# Display_Control_UV.net
KiCad netlist of a schematic drawn in Altium Designer
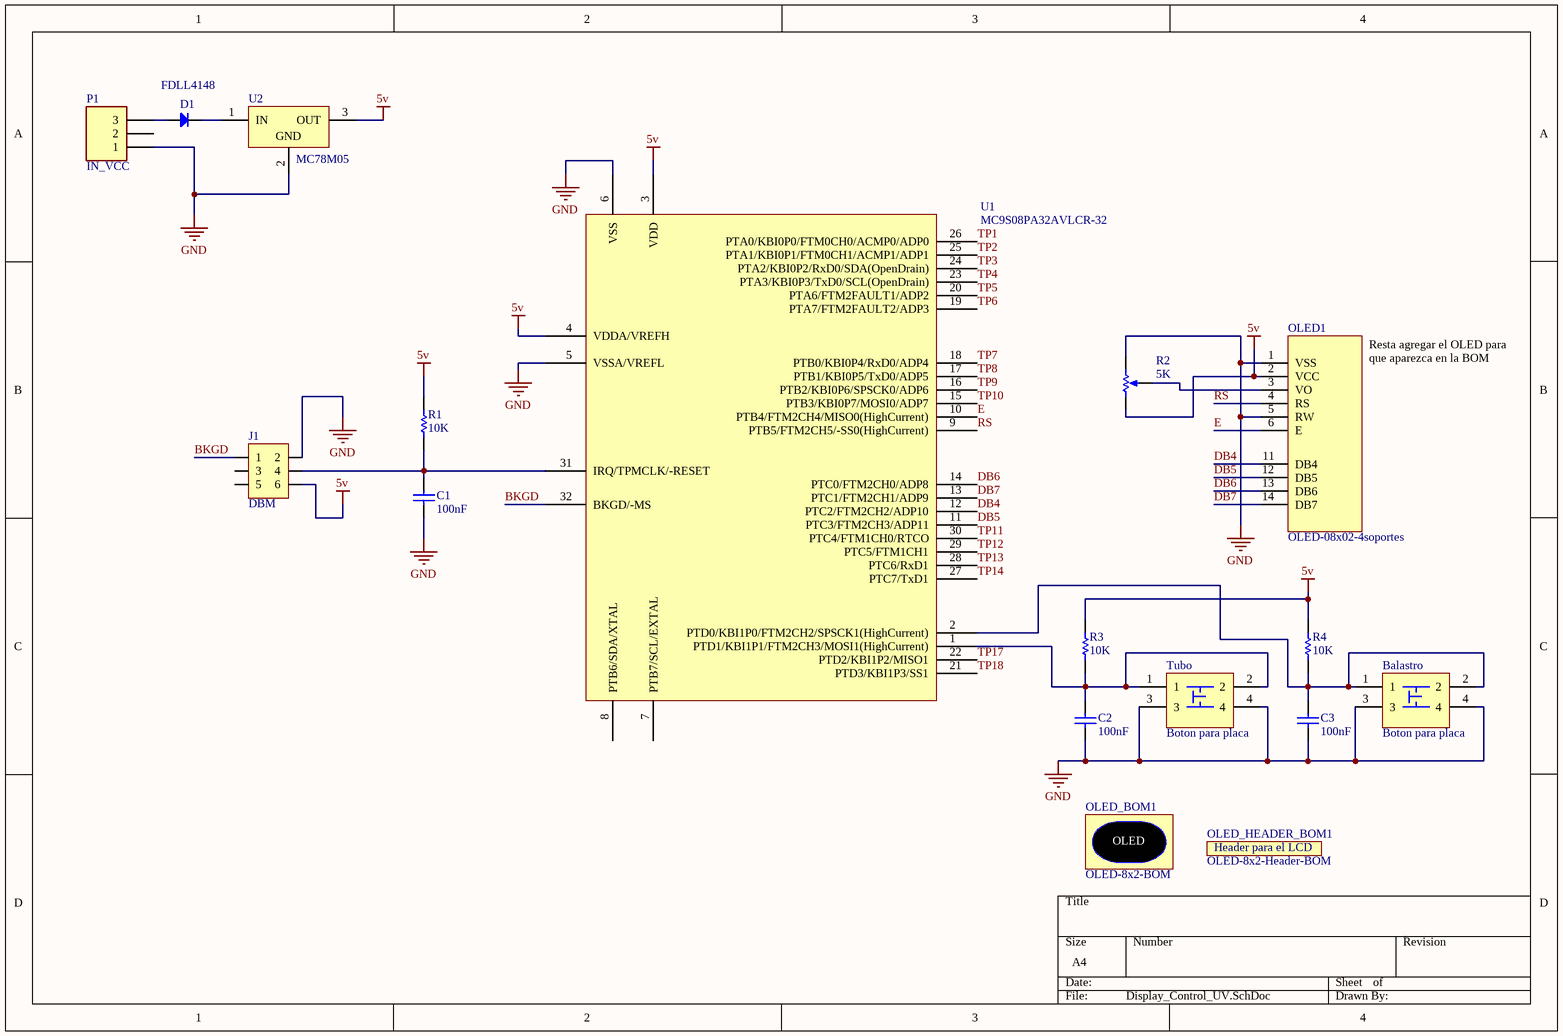
[diagram p0: Display_Control_UV.SchDoc]

(export (version "E")
  (design (tool "Eeschema 10.0.6"))
  (components
    (comp (ref "Balastro")
      (value "Boton para placa")
      (footprint "TactButton")
      (description "Ejemplo")
      (fields (field (name "PUBLISHER") "Altium Limited"))
      (libsource (lib "Nahuel_TH_BODY") (part "TactButton"))
    )
    (comp (ref "C1")
      (value "100nF")
      (footprint "Nahuel_SMD_Body:C_0603")
      (description "CAP CER 0.1UF 50V X7R 0603")
      (fields (field (name "PUBLISHER") "Altium Limited"))
      (libsource (lib "Nahuel_SMD_Body") (part "C_100nF_0603"))
    )
    (comp (ref "C2")
      (value "100nF")
      (footprint "Nahuel_SMD_Body:C_0603")
      (description "CAP CER 0.1UF 50V X7R 0603")
      (fields (field (name "PUBLISHER") "Altium Limited"))
      (libsource (lib "Nahuel_SMD_Body") (part "C_100nF_0603"))
    )
    (comp (ref "C3")
      (value "100nF")
      (footprint "Nahuel_SMD_Body:C_0603")
      (description "CAP CER 0.1UF 50V X7R 0603")
      (fields (field (name "PUBLISHER") "Altium Limited"))
      (libsource (lib "Nahuel_SMD_Body") (part "C_100nF_0603"))
    )
    (comp (ref "D1")
      (value "FDLL4148")
      (footprint "Nahuel_SMD_Body:SOD-80/MLL34")
      (description "DIODE GEN PURP 100V 200MA LL34/SOD80/MINI MELF")
      (fields (field (name "PUBLISHER") "Altium Limited"))
      (libsource (lib "Nahuel_SMD_Body") (part "Diode FDLL4148"))
    )
    (comp (ref "J1")
      (value "DBM")
      (footprint "Nahuel_TH_BODY:DBM")
      (description "CONN HEADER VERT 6POS 2.54MM")
      (fields (field (name "PUBLISHER") "Altium Limited"))
      (libsource (lib "Nahuel_TH_BODY") (part "DBM"))
    )
    (comp (ref "OLED1")
      (value "OLED-08x02-4soportes")
      (footprint "OLED-ZocaloDoble")
      (description "Header para la placa 8x2 OLED Character Display")
      (fields (field (name "PUBLISHER") "Altium Limited"))
      (libsource (lib "Nahuel_TH_BODY") (part "OLED-08x02-4soportes"))
    )
    (comp (ref "OLED_BOM1")
      (value "OLED-8x2-BOM")
      (footprint "OLED-08x02-4soportes")
      (description "8x2 OLED Character Display")
      (fields (field (name "PUBLISHER") "Altium Limited"))
      (libsource (lib "Nahuel_BOM_BODY") (part "OLED-8x2-BOM"))
    )
    (comp (ref "OLED_HEADER_BOM1")
      (value "OLED-8x2-Header-BOM")
      (description "Header 8x2")
      (fields (field (name "PUBLISHER") "Altium Limited"))
      (libsource (lib "Nahuel_BOM_BODY") (part "OLED-8x2-Header-BOM"))
    )
    (comp (ref "P1")
      (value "IN_VCC")
      (footprint "B3B-XH-A_3D")
      (description "CONN HEADER XH TOP 3POS 2.5MM")
      (fields (field (name "PUBLISHER") "Altium Limited"))
      (libsource (lib "Nahuel_Connectors_BODY") (part "JST_2.5_3"))
    )
    (comp (ref "R1")
      (value "10K")
      (footprint "Nahuel_SMD_Body:R_0603")
      (description "RES SMD 10K OHM 5% 1/10W 0603")
      (fields (field (name "PUBLISHER") "Altium Limited"))
      (libsource (lib "Nahuel_SMD_Body") (part "R_10k_0603"))
    )
    (comp (ref "R2")
      (value "5K")
      (footprint "Nahuel_SMD_Body:Preset_SMD")
      (description "TRIMMER 5K OHM 0.5W GW TOP ADJ")
      (fields (field (name "PUBLISHER") "Altium Limited"))
      (libsource (lib "Nahuel_SMD_Body") (part "Preset_5k_SMD"))
    )
    (comp (ref "R3")
      (value "10K")
      (footprint "Nahuel_SMD_Body:R_0603")
      (description "RES SMD 10K OHM 5% 1/10W 0603")
      (fields (field (name "PUBLISHER") "Altium Limited"))
      (libsource (lib "Nahuel_SMD_Body") (part "R_10k_0603"))
    )
    (comp (ref "R4")
      (value "10K")
      (footprint "Nahuel_SMD_Body:R_0603")
      (description "RES SMD 10K OHM 5% 1/10W 0603")
      (fields (field (name "PUBLISHER") "Altium Limited"))
      (libsource (lib "Nahuel_SMD_Body") (part "R_10k_0603"))
    )
    (comp (ref "Tubo")
      (value "Boton para placa")
      (footprint "TactButton")
      (description "Ejemplo")
      (fields (field (name "PUBLISHER") "Altium Limited"))
      (libsource (lib "Nahuel_TH_BODY") (part "TactButton"))
    )
    (comp (ref "U1")
      (value "MC9S08PA32AVLCR-32")
      (footprint "Nahuel_SMD_Body:QFP7x7")
      (description "S08 Microcontroller IC 8-Bit 20MHz 32KB (32K x 8) FLASH 32-LQFP (7x7)")
      (fields (field (name "PUBLISHER") "*"))
      (libsource (lib "Nahuel_SMD_Body") (part "MC9S08PA32AVLCR-32"))
    )
    (comp (ref "U2")
      (value "MC78M05")
      (footprint "Nahuel_SMD_Body:TO-252AA_N")
      (description "IC REG LINEAR 5V 500MA DPAK")
      (fields (field (name "PUBLISHER") "Altium Limited"))
      (libsource (lib "Nahuel_SMD_Body") (part "MC78M05"))
    )
  )
  (nets
    (net (code "1") (name "/BKGD") (class "Default")
      (node (ref "J1") (pin "1") (pinfunction "1_1") (pintype "passive"))
      (node (ref "U1") (pin "32") (pinfunction "BKGD/-MS_32") (pintype "passive"))
    )
    (net (code "2") (name "/DB4") (class "Default")
      (node (ref "OLED1") (pin "11") (pinfunction "DB4_11") (pintype "passive"))
      (node (ref "U1") (pin "12") (pinfunction "PTC2/FTM2CH2/ADP10_12") (pintype "passive"))
    )
    (net (code "3") (name "/DB5") (class "Default")
      (node (ref "OLED1") (pin "12") (pinfunction "DB5_12") (pintype "passive"))
      (node (ref "U1") (pin "11") (pinfunction "PTC3/FTM2CH3/ADP11_11") (pintype "passive"))
    )
    (net (code "4") (name "/DB6") (class "Default")
      (node (ref "OLED1") (pin "13") (pinfunction "DB6_13") (pintype "passive"))
      (node (ref "U1") (pin "14") (pinfunction "PTC0/FTM2CH0/ADP8_14") (pintype "passive"))
    )
    (net (code "5") (name "/DB7") (class "Default")
      (node (ref "OLED1") (pin "14") (pinfunction "DB7_14") (pintype "passive"))
      (node (ref "U1") (pin "13") (pinfunction "PTC1/FTM2CH1/ADP9_13") (pintype "passive"))
    )
    (net (code "6") (name "/E") (class "Default")
      (node (ref "OLED1") (pin "6") (pinfunction "E_6") (pintype "passive"))
      (node (ref "U1") (pin "10") (pinfunction "PTB4/FTM2CH4/MISO0(HighCurrent)_10") (pintype "passive"))
    )
    (net (code "7") (name "/RS") (class "Default")
      (node (ref "OLED1") (pin "4") (pinfunction "RS_4") (pintype "passive"))
      (node (ref "U1") (pin "9") (pinfunction "PTB5/FTM2CH5/-SS0(HighCurrent)_9") (pintype "passive"))
    )
    (net (code "8") (name "/TP1") (class "Default")
      (node (ref "U1") (pin "26") (pinfunction "PTA0/KBI0P0/FTM0CH0/ACMP0/ADP0_26") (pintype "passive"))
    )
    (net (code "9") (name "/TP2") (class "Default")
      (node (ref "U1") (pin "25") (pinfunction "PTA1/KBI0P1/FTM0CH1/ACMP1/ADP1_25") (pintype "passive"))
    )
    (net (code "10") (name "/TP3") (class "Default")
      (node (ref "U1") (pin "24") (pinfunction "PTA2/KBI0P2/RxD0/SDA(OpenDrain)_24") (pintype "passive"))
    )
    (net (code "11") (name "/TP4") (class "Default")
      (node (ref "U1") (pin "23") (pinfunction "PTA3/KBI0P3/TxD0/SCL(OpenDrain)_23") (pintype "passive"))
    )
    (net (code "12") (name "/TP5") (class "Default")
      (node (ref "U1") (pin "20") (pinfunction "PTA6/FTM2FAULT1/ADP2_20") (pintype "passive"))
    )
    (net (code "13") (name "/TP6") (class "Default")
      (node (ref "U1") (pin "19") (pinfunction "PTA7/FTM2FAULT2/ADP3_19") (pintype "passive"))
    )
    (net (code "14") (name "/TP7") (class "Default")
      (node (ref "U1") (pin "18") (pinfunction "PTB0/KBI0P4/RxD0/ADP4_18") (pintype "passive"))
    )
    (net (code "15") (name "/TP8") (class "Default")
      (node (ref "U1") (pin "17") (pinfunction "PTB1/KBI0P5/TxD0/ADP5_17") (pintype "passive"))
    )
    (net (code "16") (name "/TP9") (class "Default")
      (node (ref "U1") (pin "16") (pinfunction "PTB2/KBI0P6/SPSCK0/ADP6_16") (pintype "passive"))
    )
    (net (code "17") (name "/TP10") (class "Default")
      (node (ref "U1") (pin "15") (pinfunction "PTB3/KBI0P7/MOSI0/ADP7_15") (pintype "passive"))
    )
    (net (code "18") (name "/TP11") (class "Default")
      (node (ref "U1") (pin "30") (pinfunction "PTC4/FTM1CH0/RTCO_30") (pintype "passive"))
    )
    (net (code "19") (name "/TP12") (class "Default")
      (node (ref "U1") (pin "29") (pinfunction "PTC5/FTM1CH1_29") (pintype "passive"))
    )
    (net (code "20") (name "/TP13") (class "Default")
      (node (ref "U1") (pin "28") (pinfunction "PTC6/RxD1_28") (pintype "passive"))
    )
    (net (code "21") (name "/TP14") (class "Default")
      (node (ref "U1") (pin "27") (pinfunction "PTC7/TxD1_27") (pintype "passive"))
    )
    (net (code "22") (name "/TP17") (class "Default")
      (node (ref "U1") (pin "22") (pinfunction "PTD2/KBI1P2/MISO1_22") (pintype "passive"))
    )
    (net (code "23") (name "/TP18") (class "Default")
      (node (ref "U1") (pin "21") (pinfunction "PTD3/KBI1P3/SS1_21") (pintype "passive"))
    )
    (net (code "24") (name "5v") (class "Default")
      (node (ref "J1") (pin "6") (pinfunction "6_6") (pintype "passive"))
      (node (ref "OLED1") (pin "2") (pinfunction "VCC_2") (pintype "passive"))
      (node (ref "R1") (pin "2") (pinfunction "2_2") (pintype "passive"))
      (node (ref "R2") (pin "1") (pinfunction "TOP_CCW_1") (pintype "passive"))
      (node (ref "R3") (pin "2") (pinfunction "2_2") (pintype "passive"))
      (node (ref "R4") (pin "2") (pinfunction "2_2") (pintype "passive"))
      (node (ref "U1") (pin "3") (pinfunction "VDD_3") (pintype "passive"))
      (node (ref "U1") (pin "4") (pinfunction "VDDA/VREFH_4") (pintype "passive"))
      (node (ref "U2") (pin "3") (pinfunction "OUT_3") (pintype "power_in"))
    )
    (net (code "25") (name "GND") (class "Default")
      (node (ref "Balastro") (pin "3") (pinfunction "3_3") (pintype "passive"))
      (node (ref "Balastro") (pin "4") (pinfunction "4_4") (pintype "passive"))
      (node (ref "C1") (pin "1") (pinfunction "1_1") (pintype "passive"))
      (node (ref "C2") (pin "1") (pinfunction "1_1") (pintype "passive"))
      (node (ref "C3") (pin "1") (pinfunction "1_1") (pintype "passive"))
      (node (ref "J1") (pin "2") (pinfunction "2_2") (pintype "passive"))
      (node (ref "OLED1") (pin "1") (pinfunction "VSS_1") (pintype "passive"))
      (node (ref "OLED1") (pin "5") (pinfunction "RW_5") (pintype "passive"))
      (node (ref "P1") (pin "1") (pinfunction "1_1") (pintype "passive"))
      (node (ref "R2") (pin "3") (pinfunction "BOT_CW_3") (pintype "passive"))
      (node (ref "Tubo") (pin "3") (pinfunction "3_3") (pintype "passive"))
      (node (ref "Tubo") (pin "4") (pinfunction "4_4") (pintype "passive"))
      (node (ref "U1") (pin "5") (pinfunction "VSSA/VREFL_5") (pintype "passive"))
      (node (ref "U1") (pin "6") (pinfunction "VSS_6") (pintype "passive"))
      (node (ref "U2") (pin "2") (pinfunction "GND_2") (pintype "power_in"))
    )
    (net (code "26") (name "Net-(D1-A)") (class "Default")
      (node (ref "D1") (pin "1") (pinfunction "A_1") (pintype "passive"))
      (node (ref "P1") (pin "3") (pinfunction "3_3") (pintype "passive"))
    )
    (net (code "27") (name "Net-(D1-K)") (class "Default")
      (node (ref "D1") (pin "2") (pinfunction "K_2") (pintype "passive"))
      (node (ref "U2") (pin "1") (pinfunction "IN_1") (pintype "power_in"))
    )
    (net (code "28") (name "Net-(OLED1-VO)") (class "Default")
      (node (ref "OLED1") (pin "3") (pinfunction "VO_3") (pintype "passive"))
      (node (ref "R2") (pin "2") (pinfunction "TAP_2") (pintype "passive"))
    )
    (net (code "29") (name "Net-(U1-IRQ{slash}TPMCLK{slash}-RESET)") (class "Default")
      (node (ref "C1") (pin "2") (pinfunction "2_2") (pintype "passive"))
      (node (ref "J1") (pin "4") (pinfunction "4_4") (pintype "passive"))
      (node (ref "R1") (pin "1") (pinfunction "1_1") (pintype "passive"))
      (node (ref "U1") (pin "31") (pinfunction "IRQ/TPMCLK/-RESET_31") (pintype "passive"))
    )
    (net (code "30") (name "Net-(U1-PTD0{slash}KBI1P0{slash}FTM2CH2{slash}SPSCK1(HighCurrent))") (class "Default")
      (node (ref "Balastro") (pin "1") (pinfunction "1_1") (pintype "passive"))
      (node (ref "Balastro") (pin "2") (pinfunction "2_2") (pintype "passive"))
      (node (ref "C3") (pin "2") (pinfunction "2_2") (pintype "passive"))
      (node (ref "R4") (pin "1") (pinfunction "1_1") (pintype "passive"))
      (node (ref "U1") (pin "2") (pinfunction "PTD0/KBI1P0/FTM2CH2/SPSCK1(HighCurrent)_2") (pintype "passive"))
    )
    (net (code "31") (name "Net-(U1-PTD1{slash}KBI1P1{slash}FTM2CH3{slash}MOSI1(HighCurrent))") (class "Default")
      (node (ref "C2") (pin "2") (pinfunction "2_2") (pintype "passive"))
      (node (ref "R3") (pin "1") (pinfunction "1_1") (pintype "passive"))
      (node (ref "Tubo") (pin "1") (pinfunction "1_1") (pintype "passive"))
      (node (ref "Tubo") (pin "2") (pinfunction "2_2") (pintype "passive"))
      (node (ref "U1") (pin "1") (pinfunction "PTD1/KBI1P1/FTM2CH3/MOSI1(HighCurrent)_1") (pintype "passive"))
    )
    (net (code "32") (name "unconnected-(J1-Pad3)") (class "Default")
      (node (ref "J1") (pin "3") (pinfunction "3_3") (pintype "passive"))
    )
    (net (code "33") (name "unconnected-(J1-Pad5)") (class "Default")
      (node (ref "J1") (pin "5") (pinfunction "5_5") (pintype "passive"))
    )
    (net (code "34") (name "unconnected-(P1-Pad2)") (class "Default")
      (node (ref "P1") (pin "2") (pinfunction "2_2") (pintype "passive"))
    )
    (net (code "35") (name "unconnected-(U1-PTB6{slash}SDA{slash}XTAL-Pad8)") (class "Default")
      (node (ref "U1") (pin "8") (pinfunction "PTB6/SDA/XTAL_8") (pintype "passive"))
    )
    (net (code "36") (name "unconnected-(U1-PTB7{slash}SCL{slash}EXTAL-Pad7)") (class "Default")
      (node (ref "U1") (pin "7") (pinfunction "PTB7/SCL/EXTAL_7") (pintype "passive"))
    )
  )
)
